# Sheet_1_2021-12-08.net
KiCad netlist of a schematic drawn in Altium Designer
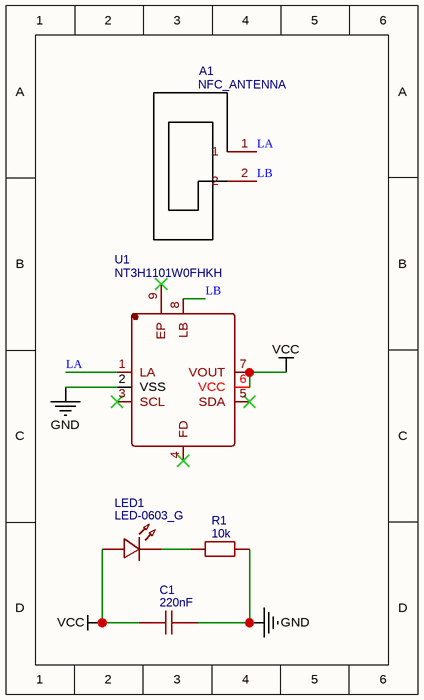
[diagram p0: Sheet_1_2021-12-08.schdoc]

(export (version "E")
  (design (tool "Eeschema 10.0.6"))
  (components
    (comp (ref "A1")
      (value "NFC_ANTENNA")
      (fields (field (name "CONTRIBUTOR") "scarrr0725"))
      (libsource (lib "altium-import") (part "root_1_NFC_ANTENNA_"))
    )
    (comp (ref "C1")
      (value "220nF")
      (fields (field (name "CONTRIBUTOR") "LCEDA_Lib"))
      (libsource (lib "altium-import") (part "root_0_220nF_"))
    )
    (comp (ref "LED1")
      (value "LED-0603_G")
      (fields
        (field (name "BOM_MANUFACTURER PART") "19-217/GHC-YR1S2/3T")
        (field (name "BOM_SUPPLIER PART") "C72043")
        (field (name "CONTRIBUTOR") "LCEDA_Lib")
      )
      (libsource (lib "altium-import") (part "root_0_LED-0603_G_"))
    )
    (comp (ref "R1")
      (value "10k")
      (fields (field (name "CONTRIBUTOR") "LCEDA_Lib"))
      (libsource (lib "altium-import") (part "root_0_10k_"))
    )
    (comp (ref "U1")
      (value "NT3H1101W0FHKH")
      (fields (field (name "BOM_SUPPLIER PART") "C73156") (field (name "CONTRIBUTOR") "LCSC"))
      (libsource (lib "altium-import") (part "root_0_NT3H1101W0FHKH_"))
    )
  )
  (nets
    (net (code "1") (name "/LA") (class "Default")
      (node (ref "A1") (pin "1") (pinfunction "1_1") (pintype "passive"))
      (node (ref "U1") (pin "1") (pinfunction "LA_1") (pintype "passive"))
    )
    (net (code "2") (name "/LB") (class "Default")
      (node (ref "A1") (pin "2") (pinfunction "2_2") (pintype "passive"))
      (node (ref "U1") (pin "8") (pinfunction "LB_8") (pintype "passive"))
    )
    (net (code "3") (name "GND") (class "Default")
      (node (ref "C1") (pin "2") (pinfunction "2_2") (pintype "passive"))
      (node (ref "R1") (pin "2") (pinfunction "2_2") (pintype "passive"))
      (node (ref "U1") (pin "2") (pinfunction "VSS_2") (pintype "passive"))
    )
    (net (code "4") (name "Net-(LED1-Pad2)") (class "Default")
      (node (ref "LED1") (pin "2") (pinfunction "2_2") (pintype "passive"))
      (node (ref "R1") (pin "1") (pinfunction "1_1") (pintype "passive"))
    )
    (net (code "5") (name "VCC") (class "Default")
      (node (ref "C1") (pin "1") (pinfunction "1_1") (pintype "passive"))
      (node (ref "LED1") (pin "1") (pinfunction "1_1") (pintype "passive"))
      (node (ref "U1") (pin "6") (pinfunction "VCC_6") (pintype "passive"))
      (node (ref "U1") (pin "7") (pinfunction "VOUT_7") (pintype "passive"))
    )
    (net (code "6") (name "unconnected-(U1-EP-Pad9)") (class "Default")
      (node (ref "U1") (pin "9") (pinfunction "EP_9") (pintype "passive+no_connect"))
    )
    (net (code "7") (name "unconnected-(U1-FD-Pad4)") (class "Default")
      (node (ref "U1") (pin "4") (pinfunction "FD_4") (pintype "passive+no_connect"))
    )
    (net (code "8") (name "unconnected-(U1-SCL-Pad3)") (class "Default")
      (node (ref "U1") (pin "3") (pinfunction "SCL_3") (pintype "passive+no_connect"))
    )
    (net (code "9") (name "unconnected-(U1-SDA-Pad5)") (class "Default")
      (node (ref "U1") (pin "5") (pinfunction "SDA_5") (pintype "passive+no_connect"))
    )
  )
)
